# TS_OD1.net
KiCad netlist of a schematic drawn in EAGLE
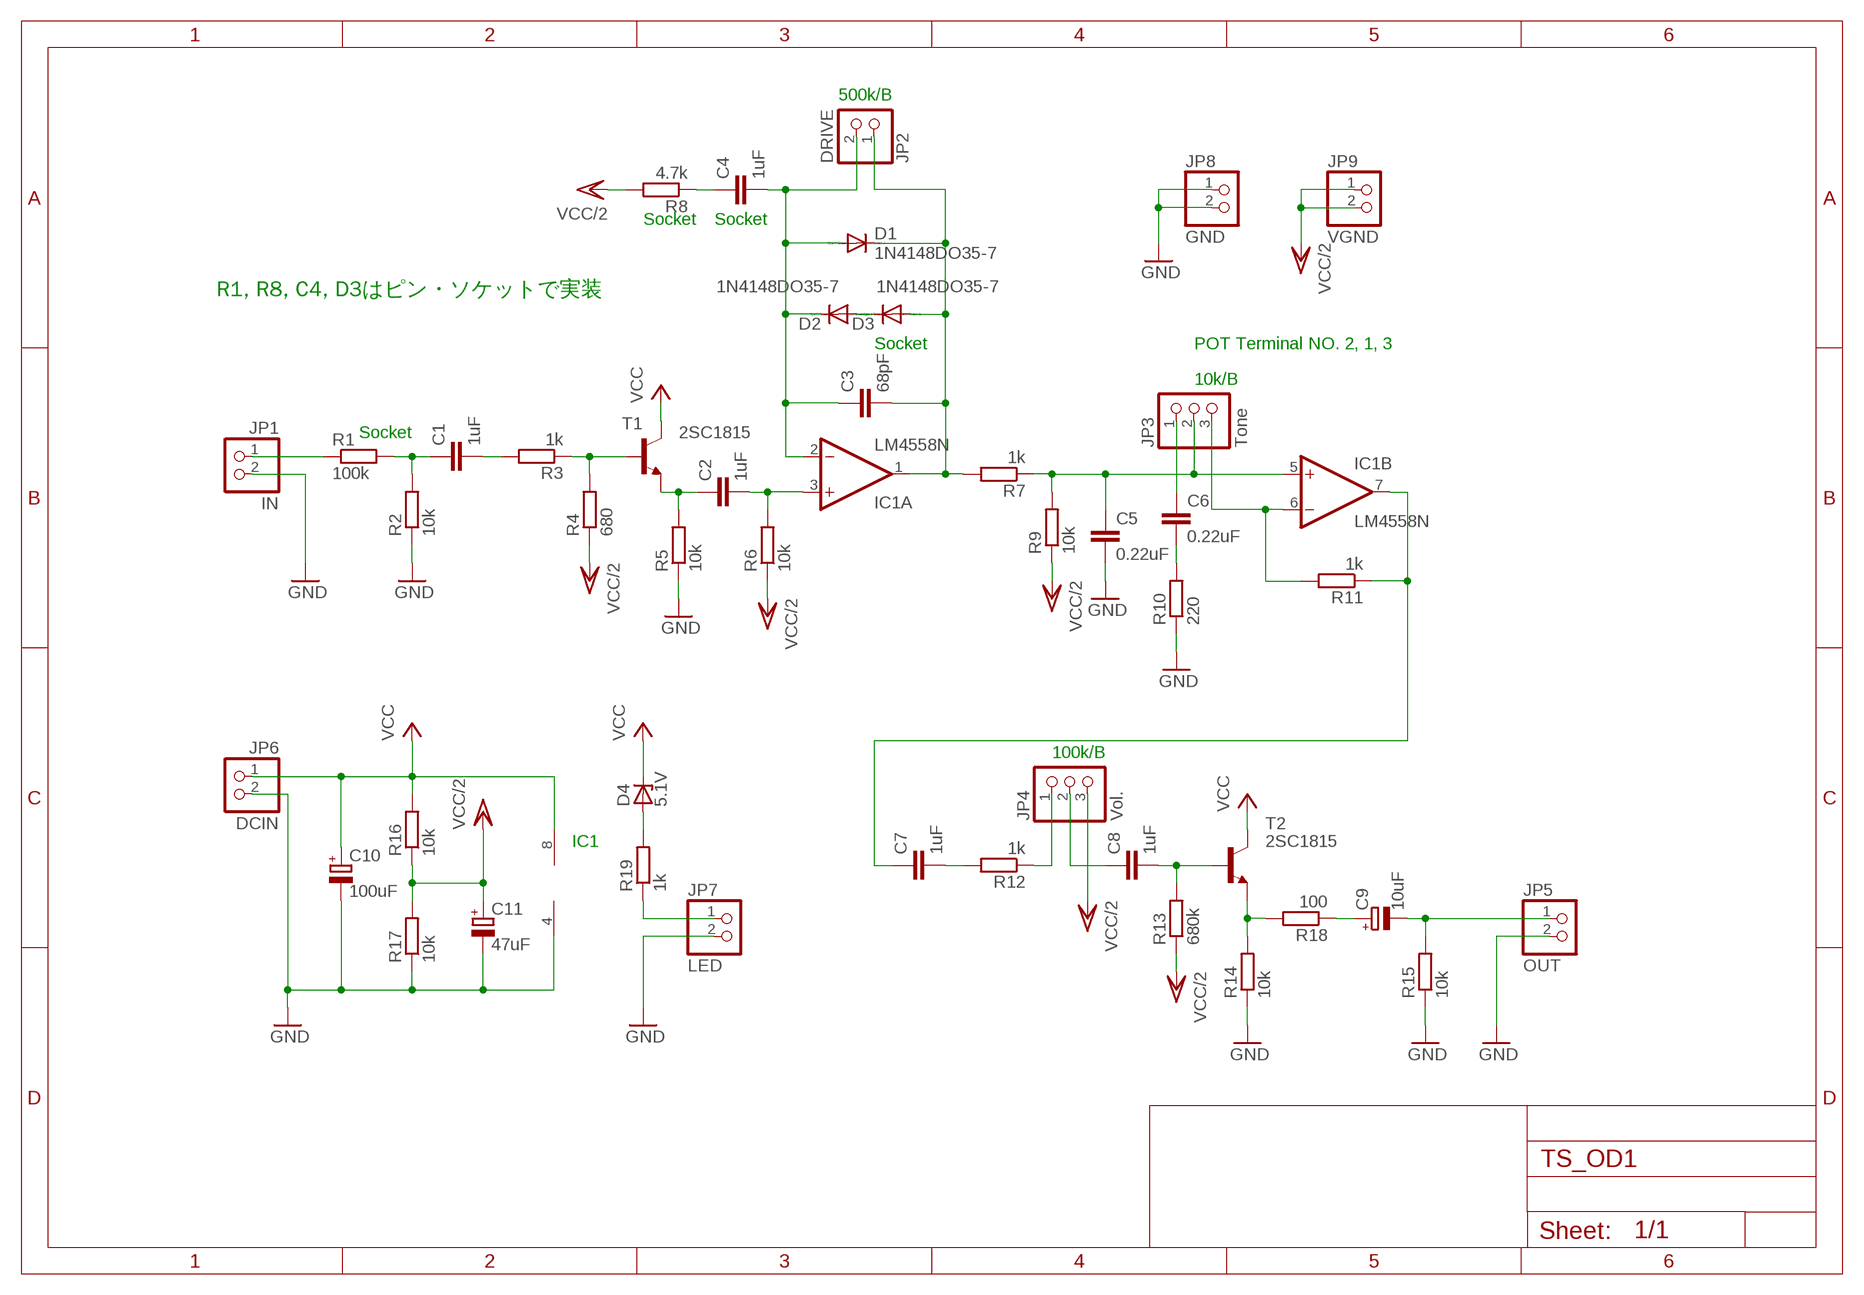
[diagram p0: schematic, sheet 1]

(export (version "E")
  (design (tool "Eeschema 10.0.6"))
  (components
    (comp (ref "C1")
      (value "1uF")
      (footprint "eagle-import:C050-050X075")
      (libsource (lib "eagle-import") (part "C-EU050-050X075"))
    )
    (comp (ref "C2")
      (value "1uF")
      (footprint "eagle-import:C050-050X075")
      (libsource (lib "eagle-import") (part "C-EU050-050X075"))
    )
    (comp (ref "C3")
      (value "68pF")
      (footprint "eagle-import:C050-024X044")
      (libsource (lib "eagle-import") (part "C-EU050-024X044"))
    )
    (comp (ref "C4")
      (value "1uF")
      (footprint "eagle-import:C050-050X075")
      (libsource (lib "eagle-import") (part "C-EU050-050X075"))
    )
    (comp (ref "C5")
      (value "0.22uF")
      (footprint "eagle-import:C050-035X075")
      (libsource (lib "eagle-import") (part "C-EU050-035X075"))
    )
    (comp (ref "C6")
      (value "0.22uF")
      (footprint "eagle-import:C050-035X075")
      (libsource (lib "eagle-import") (part "C-EU050-035X075"))
    )
    (comp (ref "C7")
      (value "1uF")
      (footprint "eagle-import:C050-050X075")
      (libsource (lib "eagle-import") (part "C-EU050-050X075"))
    )
    (comp (ref "C8")
      (value "1uF")
      (footprint "eagle-import:C050-050X075")
      (libsource (lib "eagle-import") (part "C-EU050-050X075"))
    )
    (comp (ref "C9")
      (value "10uF")
      (footprint "eagle-import:E2,5-5")
      (libsource (lib "eagle-import") (part "CPOL-EUE2.5-5"))
    )
    (comp (ref "C10")
      (value "100uF")
      (footprint "eagle-import:E5-6")
      (libsource (lib "eagle-import") (part "CPOL-EUE5-6"))
    )
    (comp (ref "C11")
      (value "47uF")
      (footprint "eagle-import:E5-6")
      (libsource (lib "eagle-import") (part "CPOL-EUE5-6"))
    )
    (comp (ref "D1")
      (value "1N4148DO35-7")
      (footprint "eagle-import:DO35-7")
      (libsource (lib "eagle-import") (part "1N4148DO35-7"))
    )
    (comp (ref "D2")
      (value "1N4148DO35-7")
      (footprint "eagle-import:DO35-7")
      (libsource (lib "eagle-import") (part "1N4148DO35-7"))
    )
    (comp (ref "D3")
      (value "1N4148DO35-7")
      (footprint "eagle-import:DO35-7")
      (libsource (lib "eagle-import") (part "1N4148DO35-7"))
    )
    (comp (ref "D4")
      (value "5.1V")
      (footprint "eagle-import:ZDIO-7.5")
      (libsource (lib "eagle-import") (part "ZENER-DIODEZD-7.5"))
    )
    (comp (ref "IC1")
      (value "LM4558N")
      (footprint "eagle-import:DIL08")
      (libsource (lib "eagle-import") (part "4558NLM"))
    )
    (comp (ref "JP1")
      (value "IN")
      (footprint "eagle-import:1X02")
      (libsource (lib "eagle-import") (part "PINHD-1X2"))
    )
    (comp (ref "JP2")
      (value "DRIVE")
      (footprint "eagle-import:1X02")
      (libsource (lib "eagle-import") (part "PINHD-1X2"))
    )
    (comp (ref "JP3")
      (value "Tone")
      (footprint "eagle-import:1X03")
      (libsource (lib "eagle-import") (part "PINHD-1X3"))
    )
    (comp (ref "JP4")
      (value "Vol.")
      (footprint "eagle-import:1X03")
      (libsource (lib "eagle-import") (part "PINHD-1X3"))
    )
    (comp (ref "JP5")
      (value "OUT")
      (footprint "eagle-import:1X02")
      (libsource (lib "eagle-import") (part "PINHD-1X2"))
    )
    (comp (ref "JP6")
      (value "DCIN")
      (footprint "eagle-import:1X02")
      (libsource (lib "eagle-import") (part "PINHD-1X2"))
    )
    (comp (ref "JP7")
      (value "LED")
      (footprint "eagle-import:1X02")
      (libsource (lib "eagle-import") (part "PINHD-1X2"))
    )
    (comp (ref "JP8")
      (value "GND")
      (footprint "eagle-import:1X02")
      (libsource (lib "eagle-import") (part "PINHD-1X2"))
    )
    (comp (ref "JP9")
      (value "VGND")
      (footprint "eagle-import:1X02")
      (libsource (lib "eagle-import") (part "PINHD-1X2"))
    )
    (comp (ref "R1")
      (value "100k")
      (footprint "eagle-import:0207_7")
      (libsource (lib "eagle-import") (part "R-EU_0207/7"))
    )
    (comp (ref "R2")
      (value "10k")
      (footprint "eagle-import:0207_7")
      (libsource (lib "eagle-import") (part "R-EU_0207/7"))
    )
    (comp (ref "R3")
      (value "1k")
      (footprint "eagle-import:0207_7")
      (libsource (lib "eagle-import") (part "R-EU_0207/7"))
    )
    (comp (ref "R4")
      (value "680")
      (footprint "eagle-import:0207_7")
      (libsource (lib "eagle-import") (part "R-EU_0207/7"))
    )
    (comp (ref "R5")
      (value "10k")
      (footprint "eagle-import:0207_7")
      (libsource (lib "eagle-import") (part "R-EU_0207/7"))
    )
    (comp (ref "R6")
      (value "10k")
      (footprint "eagle-import:0207_7")
      (libsource (lib "eagle-import") (part "R-EU_0207/7"))
    )
    (comp (ref "R7")
      (value "1k")
      (footprint "eagle-import:0207_10")
      (libsource (lib "eagle-import") (part "R-EU_0207/10"))
    )
    (comp (ref "R8")
      (value "4.7k")
      (footprint "eagle-import:0207_7")
      (libsource (lib "eagle-import") (part "R-EU_0207/7"))
    )
    (comp (ref "R9")
      (value "10k")
      (footprint "eagle-import:0207_7")
      (libsource (lib "eagle-import") (part "R-EU_0207/7"))
    )
    (comp (ref "R10")
      (value "220")
      (footprint "eagle-import:0207_7")
      (libsource (lib "eagle-import") (part "R-EU_0207/7"))
    )
    (comp (ref "R11")
      (value "1k")
      (footprint "eagle-import:0207_7")
      (libsource (lib "eagle-import") (part "R-EU_0207/7"))
    )
    (comp (ref "R12")
      (value "1k")
      (footprint "eagle-import:0207_7")
      (libsource (lib "eagle-import") (part "R-EU_0207/7"))
    )
    (comp (ref "R13")
      (value "680k")
      (footprint "eagle-import:0207_7")
      (libsource (lib "eagle-import") (part "R-EU_0207/7"))
    )
    (comp (ref "R14")
      (value "10k")
      (footprint "eagle-import:0207_7")
      (libsource (lib "eagle-import") (part "R-EU_0207/7"))
    )
    (comp (ref "R15")
      (value "10k")
      (footprint "eagle-import:0207_7")
      (libsource (lib "eagle-import") (part "R-EU_0207/7"))
    )
    (comp (ref "R16")
      (value "10k")
      (footprint "eagle-import:0207_7")
      (libsource (lib "eagle-import") (part "R-EU_0207/7"))
    )
    (comp (ref "R17")
      (value "10k")
      (footprint "eagle-import:0207_7")
      (libsource (lib "eagle-import") (part "R-EU_0207/7"))
    )
    (comp (ref "R18")
      (value "100")
      (footprint "eagle-import:0207_7")
      (libsource (lib "eagle-import") (part "R-EU_0207/7"))
    )
    (comp (ref "R19")
      (value "1k")
      (footprint "eagle-import:0207_7")
      (libsource (lib "eagle-import") (part "R-EU_0207/7"))
    )
    (comp (ref "T1")
      (value "2SC1815")
      (footprint "eagle-import:TO92-ECB")
      (libsource (lib "eagle-import") (part "-NPN-TO92-ECB"))
    )
    (comp (ref "T2")
      (value "2SC1815")
      (footprint "eagle-import:TO92-ECB")
      (libsource (lib "eagle-import") (part "-NPN-TO92-ECB"))
    )
  )
  (nets
    (net (code "1") (name "GND") (class "Default")
      (node (ref "C10") (pin "-") (pinfunction "-_-") (pintype "passive"))
      (node (ref "C11") (pin "-") (pinfunction "-_-") (pintype "passive"))
      (node (ref "C5") (pin "2") (pinfunction "2_2") (pintype "passive"))
      (node (ref "IC1") (pin "4") (pinfunction "V-_4") (pintype "power_in"))
      (node (ref "JP1") (pin "2") (pinfunction "2_2") (pintype "passive"))
      (node (ref "JP5") (pin "2") (pinfunction "2_2") (pintype "passive"))
      (node (ref "JP6") (pin "2") (pinfunction "2_2") (pintype "passive"))
      (node (ref "JP7") (pin "2") (pinfunction "2_2") (pintype "passive"))
      (node (ref "JP8") (pin "1") (pinfunction "1_1") (pintype "passive"))
      (node (ref "JP8") (pin "2") (pinfunction "2_2") (pintype "passive"))
      (node (ref "R10") (pin "1") (pinfunction "1_1") (pintype "passive"))
      (node (ref "R14") (pin "1") (pinfunction "1_1") (pintype "passive"))
      (node (ref "R15") (pin "1") (pinfunction "1_1") (pintype "passive"))
      (node (ref "R17") (pin "1") (pinfunction "1_1") (pintype "passive"))
      (node (ref "R2") (pin "1") (pinfunction "1_1") (pintype "passive"))
      (node (ref "R5") (pin "1") (pinfunction "1_1") (pintype "passive"))
    )
    (net (code "2") (name "Net-(C1-Pad1)") (class "Default")
      (node (ref "C1") (pin "1") (pinfunction "1_1") (pintype "passive"))
      (node (ref "R1") (pin "2") (pinfunction "2_2") (pintype "passive"))
      (node (ref "R2") (pin "2") (pinfunction "2_2") (pintype "passive"))
    )
    (net (code "3") (name "Net-(C1-Pad2)") (class "Default")
      (node (ref "C1") (pin "2") (pinfunction "2_2") (pintype "passive"))
      (node (ref "R3") (pin "2") (pinfunction "2_2") (pintype "passive"))
    )
    (net (code "4") (name "Net-(C2-Pad1)") (class "Default")
      (node (ref "C2") (pin "1") (pinfunction "1_1") (pintype "passive"))
      (node (ref "R5") (pin "2") (pinfunction "2_2") (pintype "passive"))
      (node (ref "T1") (pin "E") (pinfunction "E_E") (pintype "passive"))
    )
    (net (code "5") (name "Net-(C4-Pad1)") (class "Default")
      (node (ref "C4") (pin "1") (pinfunction "1_1") (pintype "passive"))
      (node (ref "R8") (pin "1") (pinfunction "1_1") (pintype "passive"))
    )
    (net (code "6") (name "Net-(C6-Pad1)") (class "Default")
      (node (ref "C6") (pin "1") (pinfunction "1_1") (pintype "passive"))
      (node (ref "JP3") (pin "1") (pinfunction "1_1") (pintype "passive"))
    )
    (net (code "7") (name "Net-(C6-Pad2)") (class "Default")
      (node (ref "C6") (pin "2") (pinfunction "2_2") (pintype "passive"))
      (node (ref "R10") (pin "2") (pinfunction "2_2") (pintype "passive"))
    )
    (net (code "8") (name "Net-(C7-Pad2)") (class "Default")
      (node (ref "C7") (pin "2") (pinfunction "2_2") (pintype "passive"))
      (node (ref "R12") (pin "2") (pinfunction "2_2") (pintype "passive"))
    )
    (net (code "9") (name "Net-(C8-Pad1)") (class "Default")
      (node (ref "C8") (pin "1") (pinfunction "1_1") (pintype "passive"))
      (node (ref "JP4") (pin "2") (pinfunction "2_2") (pintype "passive"))
    )
    (net (code "10") (name "Net-(C8-Pad2)") (class "Default")
      (node (ref "C8") (pin "2") (pinfunction "2_2") (pintype "passive"))
      (node (ref "R13") (pin "2") (pinfunction "2_2") (pintype "passive"))
      (node (ref "T2") (pin "B") (pinfunction "B_B") (pintype "passive"))
    )
    (net (code "11") (name "Net-(C9-Pad+)") (class "Default")
      (node (ref "C9") (pin "+") (pinfunction "+_+") (pintype "passive"))
      (node (ref "R18") (pin "1") (pinfunction "1_1") (pintype "passive"))
    )
    (net (code "12") (name "Net-(C9-Pad-)") (class "Default")
      (node (ref "C9") (pin "-") (pinfunction "-_-") (pintype "passive"))
      (node (ref "JP5") (pin "1") (pinfunction "1_1") (pintype "passive"))
      (node (ref "R15") (pin "2") (pinfunction "2_2") (pintype "passive"))
    )
    (net (code "13") (name "Net-(D2-PadA)") (class "Default")
      (node (ref "D2") (pin "A") (pinfunction "A_A") (pintype "passive"))
      (node (ref "D3") (pin "C") (pinfunction "C_C") (pintype "passive"))
    )
    (net (code "14") (name "Net-(D4-PadA)") (class "Default")
      (node (ref "D4") (pin "A") (pinfunction "A_A") (pintype "passive"))
      (node (ref "R19") (pin "2") (pinfunction "2_2") (pintype "passive"))
    )
    (net (code "15") (name "Net-(IC1A-+IN)") (class "Default")
      (node (ref "C2") (pin "2") (pinfunction "2_2") (pintype "passive"))
      (node (ref "IC1") (pin "3") (pinfunction "+IN_3") (pintype "input"))
      (node (ref "R6") (pin "2") (pinfunction "2_2") (pintype "passive"))
    )
    (net (code "16") (name "Net-(IC1A--IN)") (class "Default")
      (node (ref "C3") (pin "1") (pinfunction "1_1") (pintype "passive"))
      (node (ref "C4") (pin "2") (pinfunction "2_2") (pintype "passive"))
      (node (ref "D1") (pin "A") (pinfunction "A_A") (pintype "passive"))
      (node (ref "D2") (pin "C") (pinfunction "C_C") (pintype "passive"))
      (node (ref "IC1") (pin "2") (pinfunction "-IN_2") (pintype "input"))
      (node (ref "JP2") (pin "2") (pinfunction "2_2") (pintype "passive"))
    )
    (net (code "17") (name "Net-(IC1A-OUT)") (class "Default")
      (node (ref "C3") (pin "2") (pinfunction "2_2") (pintype "passive"))
      (node (ref "D1") (pin "C") (pinfunction "C_C") (pintype "passive"))
      (node (ref "D3") (pin "A") (pinfunction "A_A") (pintype "passive"))
      (node (ref "IC1") (pin "1") (pinfunction "OUT_1") (pintype "output"))
      (node (ref "JP2") (pin "1") (pinfunction "1_1") (pintype "passive"))
      (node (ref "R7") (pin "2") (pinfunction "2_2") (pintype "passive"))
    )
    (net (code "18") (name "Net-(IC1B-+IN)") (class "Default")
      (node (ref "C5") (pin "1") (pinfunction "1_1") (pintype "passive"))
      (node (ref "IC1") (pin "5") (pinfunction "+IN_5") (pintype "input"))
      (node (ref "JP3") (pin "2") (pinfunction "2_2") (pintype "passive"))
      (node (ref "R7") (pin "1") (pinfunction "1_1") (pintype "passive"))
      (node (ref "R9") (pin "2") (pinfunction "2_2") (pintype "passive"))
    )
    (net (code "19") (name "Net-(IC1B--IN)") (class "Default")
      (node (ref "IC1") (pin "6") (pinfunction "-IN_6") (pintype "input"))
      (node (ref "JP3") (pin "3") (pinfunction "3_3") (pintype "passive"))
      (node (ref "R11") (pin "2") (pinfunction "2_2") (pintype "passive"))
    )
    (net (code "20") (name "Net-(IC1B-OUT)") (class "Default")
      (node (ref "C7") (pin "1") (pinfunction "1_1") (pintype "passive"))
      (node (ref "IC1") (pin "7") (pinfunction "OUT_7") (pintype "output"))
      (node (ref "R11") (pin "1") (pinfunction "1_1") (pintype "passive"))
    )
    (net (code "21") (name "Net-(JP1-Pad1)") (class "Default")
      (node (ref "JP1") (pin "1") (pinfunction "1_1") (pintype "passive"))
      (node (ref "R1") (pin "1") (pinfunction "1_1") (pintype "passive"))
    )
    (net (code "22") (name "Net-(JP4-Pad1)") (class "Default")
      (node (ref "JP4") (pin "1") (pinfunction "1_1") (pintype "passive"))
      (node (ref "R12") (pin "1") (pinfunction "1_1") (pintype "passive"))
    )
    (net (code "23") (name "Net-(JP7-Pad1)") (class "Default")
      (node (ref "JP7") (pin "1") (pinfunction "1_1") (pintype "passive"))
      (node (ref "R19") (pin "1") (pinfunction "1_1") (pintype "passive"))
    )
    (net (code "24") (name "Net-(R3-Pad1)") (class "Default")
      (node (ref "R3") (pin "1") (pinfunction "1_1") (pintype "passive"))
      (node (ref "R4") (pin "2") (pinfunction "2_2") (pintype "passive"))
      (node (ref "T1") (pin "B") (pinfunction "B_B") (pintype "passive"))
    )
    (net (code "25") (name "Net-(R14-Pad2)") (class "Default")
      (node (ref "R14") (pin "2") (pinfunction "2_2") (pintype "passive"))
      (node (ref "R18") (pin "2") (pinfunction "2_2") (pintype "passive"))
      (node (ref "T2") (pin "E") (pinfunction "E_E") (pintype "passive"))
    )
    (net (code "26") (name "VCC") (class "Default")
      (node (ref "C10") (pin "+") (pinfunction "+_+") (pintype "passive"))
      (node (ref "D4") (pin "C") (pinfunction "C_C") (pintype "passive"))
      (node (ref "IC1") (pin "8") (pinfunction "V+_8") (pintype "power_in"))
      (node (ref "JP6") (pin "1") (pinfunction "1_1") (pintype "passive"))
      (node (ref "R16") (pin "2") (pinfunction "2_2") (pintype "passive"))
      (node (ref "T1") (pin "C") (pinfunction "C_C") (pintype "passive"))
      (node (ref "T2") (pin "C") (pinfunction "C_C") (pintype "passive"))
    )
    (net (code "27") (name "VCC{slash}2") (class "Default")
      (node (ref "C11") (pin "+") (pinfunction "+_+") (pintype "passive"))
      (node (ref "JP4") (pin "3") (pinfunction "3_3") (pintype "passive"))
      (node (ref "JP9") (pin "1") (pinfunction "1_1") (pintype "passive"))
      (node (ref "JP9") (pin "2") (pinfunction "2_2") (pintype "passive"))
      (node (ref "R13") (pin "1") (pinfunction "1_1") (pintype "passive"))
      (node (ref "R16") (pin "1") (pinfunction "1_1") (pintype "passive"))
      (node (ref "R17") (pin "2") (pinfunction "2_2") (pintype "passive"))
      (node (ref "R4") (pin "1") (pinfunction "1_1") (pintype "passive"))
      (node (ref "R6") (pin "1") (pinfunction "1_1") (pintype "passive"))
      (node (ref "R8") (pin "2") (pinfunction "2_2") (pintype "passive"))
      (node (ref "R9") (pin "1") (pinfunction "1_1") (pintype "passive"))
    )
  )
)
